# M220noadder.net
KiCad netlist of a schematic drawn in EAGLE
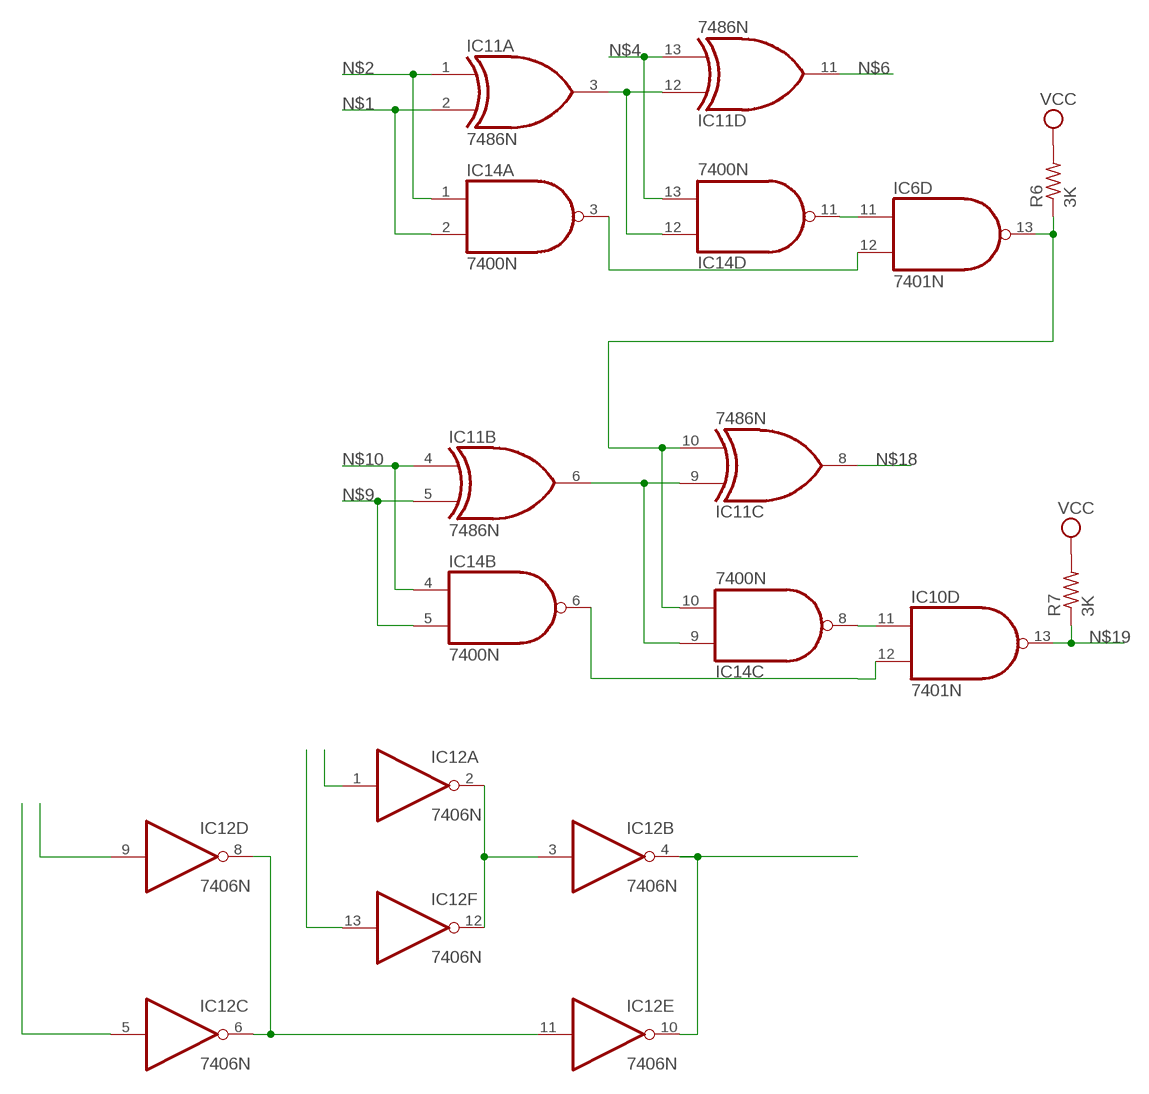
[diagram p0: schematic, sheet 1, part 1 of 2]
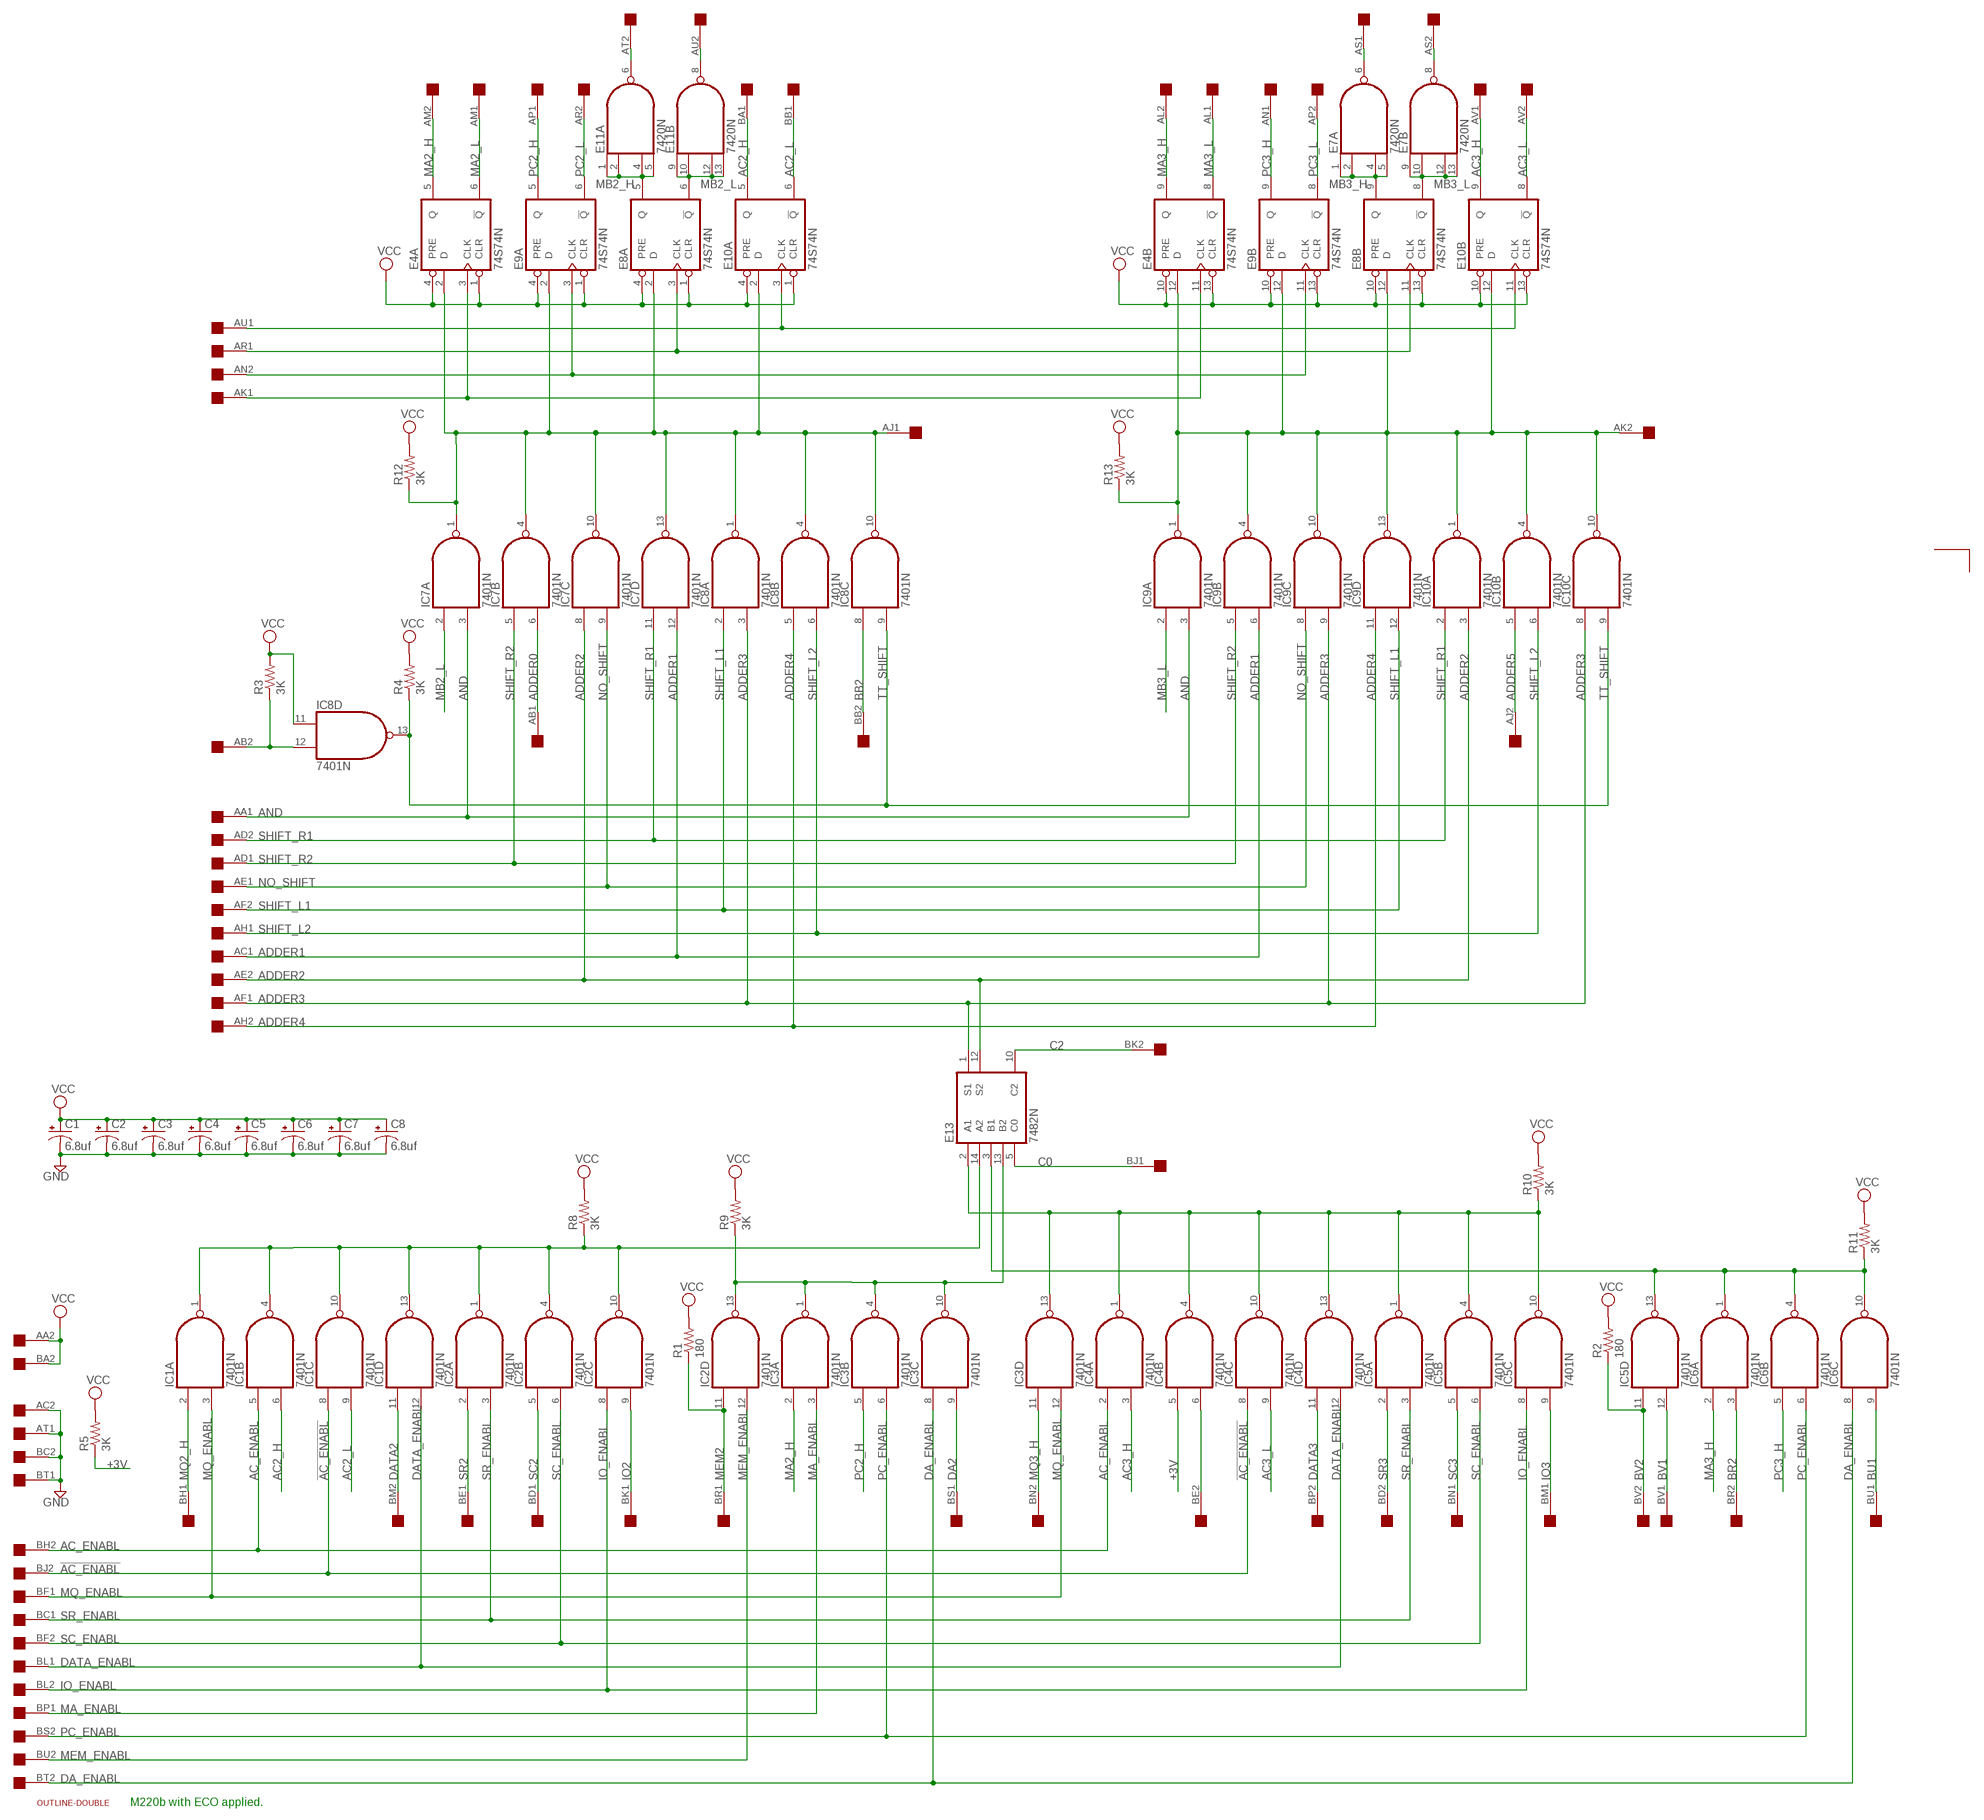
[diagram p1: schematic, sheet 1, part 2 of 2]

(export (version "E")
  (design (tool "Eeschema 10.0.6"))
  (components
    (comp (ref "C1")
      (value "6.8uf")
      (footprint "eagle-import:E15-5")
      (libsource (lib "eagle-import") (part "CPOL-USE15-5AXIAL"))
    )
    (comp (ref "C2")
      (value "6.8uf")
      (footprint "eagle-import:E15-5")
      (libsource (lib "eagle-import") (part "CPOL-USE15-5AXIAL"))
    )
    (comp (ref "C3")
      (value "6.8uf")
      (footprint "eagle-import:E15-5")
      (libsource (lib "eagle-import") (part "CPOL-USE15-5AXIAL"))
    )
    (comp (ref "C4")
      (value "6.8uf")
      (footprint "eagle-import:E15-5")
      (libsource (lib "eagle-import") (part "CPOL-USE15-5AXIAL"))
    )
    (comp (ref "C5")
      (value "6.8uf")
      (footprint "eagle-import:E15-5")
      (libsource (lib "eagle-import") (part "CPOL-USE15-5AXIAL"))
    )
    (comp (ref "C6")
      (value "6.8uf")
      (footprint "eagle-import:E15-5")
      (libsource (lib "eagle-import") (part "CPOL-USE15-5AXIAL"))
    )
    (comp (ref "C7")
      (value "6.8uf")
      (footprint "eagle-import:E15-5")
      (libsource (lib "eagle-import") (part "CPOL-USE15-5AXIAL"))
    )
    (comp (ref "C8")
      (value "6.8uf")
      (footprint "eagle-import:E15-5")
      (libsource (lib "eagle-import") (part "CPOL-USE15-5AXIAL"))
    )
    (comp (ref "E4")
      (value "74S74N")
      (footprint "eagle-import:DIL14")
      (libsource (lib "eagle-import") (part "7474NS"))
    )
    (comp (ref "E7")
      (value "7420N")
      (footprint "eagle-import:DIL14")
      (libsource (lib "eagle-import") (part "7420NS"))
    )
    (comp (ref "E8")
      (value "74S74N")
      (footprint "eagle-import:DIL14")
      (libsource (lib "eagle-import") (part "7474NS"))
    )
    (comp (ref "E9")
      (value "74S74N")
      (footprint "eagle-import:DIL14")
      (libsource (lib "eagle-import") (part "7474NS"))
    )
    (comp (ref "E10")
      (value "74S74N")
      (footprint "eagle-import:DIL14")
      (libsource (lib "eagle-import") (part "7474NS"))
    )
    (comp (ref "E11")
      (value "7420N")
      (footprint "eagle-import:DIL14")
      (libsource (lib "eagle-import") (part "7420NS"))
    )
    (comp (ref "E13")
      (value "7482N")
      (footprint "eagle-import:DIL14")
      (libsource (lib "eagle-import") (part "7482N"))
    )
    (comp (ref "IC1")
      (value "7401N")
      (footprint "eagle-import:DIL14")
      (libsource (lib "eagle-import") (part "7401N"))
    )
    (comp (ref "IC2")
      (value "7401N")
      (footprint "eagle-import:DIL14")
      (libsource (lib "eagle-import") (part "7401N"))
    )
    (comp (ref "IC3")
      (value "7401N")
      (footprint "eagle-import:DIL14")
      (libsource (lib "eagle-import") (part "7401N"))
    )
    (comp (ref "IC4")
      (value "7401N")
      (footprint "eagle-import:DIL14")
      (libsource (lib "eagle-import") (part "7401N"))
    )
    (comp (ref "IC5")
      (value "7401N")
      (footprint "eagle-import:DIL14")
      (libsource (lib "eagle-import") (part "7401N"))
    )
    (comp (ref "IC6")
      (value "7401N")
      (footprint "eagle-import:DIL14")
      (libsource (lib "eagle-import") (part "7401N"))
    )
    (comp (ref "IC7")
      (value "7401N")
      (footprint "eagle-import:DIL14")
      (libsource (lib "eagle-import") (part "7401N"))
    )
    (comp (ref "IC8")
      (value "7401N")
      (footprint "eagle-import:DIL14")
      (libsource (lib "eagle-import") (part "7401N"))
    )
    (comp (ref "IC9")
      (value "7401N")
      (footprint "eagle-import:DIL14")
      (libsource (lib "eagle-import") (part "7401N"))
    )
    (comp (ref "IC10")
      (value "7401N")
      (footprint "eagle-import:DIL14")
      (libsource (lib "eagle-import") (part "7401N"))
    )
    (comp (ref "IC11")
      (value "7486N")
      (footprint "eagle-import:DIL14")
      (libsource (lib "eagle-import") (part "7486N"))
    )
    (comp (ref "IC12")
      (value "7406N")
      (footprint "eagle-import:DIL14")
      (libsource (lib "eagle-import") (part "7406N"))
    )
    (comp (ref "IC14")
      (value "7400N")
      (footprint "eagle-import:DIL14")
      (libsource (lib "eagle-import") (part "7400N"))
    )
    (comp (ref "R1")
      (value "180")
      (footprint "eagle-import:0207_10")
      (libsource (lib "eagle-import") (part "R-US_0207/10"))
    )
    (comp (ref "R2")
      (value "180")
      (footprint "eagle-import:0207_10")
      (libsource (lib "eagle-import") (part "R-US_0207/10"))
    )
    (comp (ref "R3")
      (value "3K")
      (footprint "eagle-import:0207_10")
      (libsource (lib "eagle-import") (part "R-US_0207/10"))
    )
    (comp (ref "R4")
      (value "3K")
      (footprint "eagle-import:0207_10")
      (libsource (lib "eagle-import") (part "R-US_0207/10"))
    )
    (comp (ref "R5")
      (value "3K")
      (footprint "eagle-import:0207_10")
      (libsource (lib "eagle-import") (part "R-US_0207/10"))
    )
    (comp (ref "R6")
      (value "3K")
      (footprint "eagle-import:0207_10")
      (libsource (lib "eagle-import") (part "R-US_0207/10"))
    )
    (comp (ref "R7")
      (value "3K")
      (footprint "eagle-import:0207_10")
      (libsource (lib "eagle-import") (part "R-US_0207/10"))
    )
    (comp (ref "R8")
      (value "3K")
      (footprint "eagle-import:0207_10")
      (libsource (lib "eagle-import") (part "R-US_0207/10"))
    )
    (comp (ref "R9")
      (value "3K")
      (footprint "eagle-import:0207_10")
      (libsource (lib "eagle-import") (part "R-US_0207/10"))
    )
    (comp (ref "R10")
      (value "3K")
      (footprint "eagle-import:0207_10")
      (libsource (lib "eagle-import") (part "R-US_0207/10"))
    )
    (comp (ref "R11")
      (value "3K")
      (footprint "eagle-import:0207_10")
      (libsource (lib "eagle-import") (part "R-US_0207/10"))
    )
    (comp (ref "R12")
      (value "3K")
      (footprint "eagle-import:0207_10")
      (libsource (lib "eagle-import") (part "R-US_0207/10"))
    )
    (comp (ref "R13")
      (value "3K")
      (footprint "eagle-import:0207_10")
      (libsource (lib "eagle-import") (part "R-US_0207/10"))
    )
    (comp (ref "U$1")
      (value "DOUBLE")
      (footprint "eagle-import:EDGE-CON4")
      (libsource (lib "eagle-import") (part "DOUBLE"))
    )
    (comp (ref "U$2")
      (value "OUTLINE-DOUBLE")
      (footprint "eagle-import:DOUBLE")
      (libsource (lib "eagle-import") (part "OUTLINE-DOUBLE"))
    )
  )
  (nets
    (net (code "1") (name "/+3V") (class "Default")
      (node (ref "IC4") (pin "5") (pinfunction "I0_5") (pintype "input"))
      (node (ref "R5") (pin "1") (pinfunction "1_1") (pintype "passive"))
    )
    (net (code "2") (name "/AC2_H") (class "Default")
      (node (ref "E10") (pin "5") (pinfunction "Q_5") (pintype "output"))
      (node (ref "IC1") (pin "6") (pinfunction "I1_6") (pintype "input"))
      (node (ref "U$1") (pin "BA1") (pinfunction "1_BA1") (pintype "passive"))
    )
    (net (code "3") (name "/AC2_L") (class "Default")
      (node (ref "E10") (pin "6") (pinfunction "~{Q}_6") (pintype "output"))
      (node (ref "IC1") (pin "9") (pinfunction "I1_9") (pintype "input"))
      (node (ref "U$1") (pin "BB1") (pinfunction "1_BB1") (pintype "passive"))
    )
    (net (code "4") (name "/AC3_H") (class "Default")
      (node (ref "E10") (pin "9") (pinfunction "Q_9") (pintype "output"))
      (node (ref "IC4") (pin "3") (pinfunction "I1_3") (pintype "input"))
      (node (ref "U$1") (pin "AV1") (pinfunction "1_AV1") (pintype "passive"))
    )
    (net (code "5") (name "/AC3_L") (class "Default")
      (node (ref "E10") (pin "8") (pinfunction "~{Q}_8") (pintype "output"))
      (node (ref "IC4") (pin "9") (pinfunction "I1_9") (pintype "input"))
      (node (ref "U$1") (pin "AV2") (pinfunction "1_AV2") (pintype "passive"))
    )
    (net (code "6") (name "/AC_ENABL") (class "Default")
      (node (ref "IC1") (pin "5") (pinfunction "I0_5") (pintype "input"))
      (node (ref "IC4") (pin "2") (pinfunction "I0_2") (pintype "input"))
      (node (ref "U$1") (pin "BH2") (pinfunction "1_BH2") (pintype "passive"))
    )
    (net (code "7") (name "/ADDER0") (class "Default")
      (node (ref "IC7") (pin "6") (pinfunction "I1_6") (pintype "input"))
      (node (ref "U$1") (pin "AB1") (pinfunction "1_AB1") (pintype "passive"))
    )
    (net (code "8") (name "/ADDER1") (class "Default")
      (node (ref "IC7") (pin "12") (pinfunction "I1_12") (pintype "input"))
      (node (ref "IC9") (pin "6") (pinfunction "I1_6") (pintype "input"))
      (node (ref "U$1") (pin "AC1") (pinfunction "1_AC1") (pintype "passive"))
    )
    (net (code "9") (name "/ADDER2") (class "Default")
      (node (ref "E13") (pin "12") (pinfunction "S2_12") (pintype "output"))
      (node (ref "IC10") (pin "3") (pinfunction "I1_3") (pintype "input"))
      (node (ref "IC7") (pin "8") (pinfunction "I0_8") (pintype "input"))
      (node (ref "U$1") (pin "AE2") (pinfunction "1_AE2") (pintype "passive"))
    )
    (net (code "10") (name "/ADDER3") (class "Default")
      (node (ref "E13") (pin "1") (pinfunction "S1_1") (pintype "output"))
      (node (ref "IC10") (pin "8") (pinfunction "I0_8") (pintype "input"))
      (node (ref "IC8") (pin "3") (pinfunction "I1_3") (pintype "input"))
      (node (ref "IC9") (pin "9") (pinfunction "I1_9") (pintype "input"))
      (node (ref "U$1") (pin "AF1") (pinfunction "1_AF1") (pintype "passive"))
    )
    (net (code "11") (name "/ADDER4") (class "Default")
      (node (ref "IC8") (pin "5") (pinfunction "I0_5") (pintype "input"))
      (node (ref "IC9") (pin "11") (pinfunction "I0_11") (pintype "input"))
      (node (ref "U$1") (pin "AH2") (pinfunction "1_AH2") (pintype "passive"))
    )
    (net (code "12") (name "/ADDER5") (class "Default")
      (node (ref "IC10") (pin "5") (pinfunction "I0_5") (pintype "input"))
      (node (ref "U$1") (pin "AJ2") (pinfunction "1_AJ2") (pintype "passive"))
    )
    (net (code "13") (name "/AND") (class "Default")
      (node (ref "IC7") (pin "3") (pinfunction "I1_3") (pintype "input"))
      (node (ref "IC9") (pin "3") (pinfunction "I1_3") (pintype "input"))
      (node (ref "U$1") (pin "AA1") (pinfunction "1_AA1") (pintype "passive"))
    )
    (net (code "14") (name "/BB2") (class "Default")
      (node (ref "IC8") (pin "8") (pinfunction "I0_8") (pintype "input"))
      (node (ref "U$1") (pin "BB2") (pinfunction "1_BB2") (pintype "passive"))
    )
    (net (code "15") (name "/BR2") (class "Default")
      (node (ref "IC6") (pin "3") (pinfunction "I1_3") (pintype "input"))
      (node (ref "U$1") (pin "BR2") (pinfunction "1_BR2") (pintype "passive"))
    )
    (net (code "16") (name "/BU1") (class "Default")
      (node (ref "IC6") (pin "9") (pinfunction "I1_9") (pintype "input"))
      (node (ref "U$1") (pin "BU1") (pinfunction "1_BU1") (pintype "passive"))
    )
    (net (code "17") (name "/BV1") (class "Default")
      (node (ref "IC5") (pin "12") (pinfunction "I1_12") (pintype "input"))
      (node (ref "U$1") (pin "BV1") (pinfunction "1_BV1") (pintype "passive"))
    )
    (net (code "18") (name "/BV2") (class "Default")
      (node (ref "IC5") (pin "11") (pinfunction "I0_11") (pintype "input"))
      (node (ref "R2") (pin "1") (pinfunction "1_1") (pintype "passive"))
      (node (ref "U$1") (pin "BV2") (pinfunction "1_BV2") (pintype "passive"))
    )
    (net (code "19") (name "/C0") (class "Default")
      (node (ref "E13") (pin "5") (pinfunction "C0_5") (pintype "input"))
      (node (ref "U$1") (pin "BJ1") (pinfunction "1_BJ1") (pintype "passive"))
    )
    (net (code "20") (name "/C2") (class "Default")
      (node (ref "E13") (pin "10") (pinfunction "C2_10") (pintype "output"))
      (node (ref "U$1") (pin "BK2") (pinfunction "1_BK2") (pintype "passive"))
    )
    (net (code "21") (name "/DA2") (class "Default")
      (node (ref "IC3") (pin "9") (pinfunction "I1_9") (pintype "input"))
      (node (ref "U$1") (pin "BS1") (pinfunction "1_BS1") (pintype "passive"))
    )
    (net (code "22") (name "/DATA2") (class "Default")
      (node (ref "IC1") (pin "11") (pinfunction "I0_11") (pintype "input"))
      (node (ref "U$1") (pin "BM2") (pinfunction "1_BM2") (pintype "passive"))
    )
    (net (code "23") (name "/DATA3") (class "Default")
      (node (ref "IC4") (pin "11") (pinfunction "I0_11") (pintype "input"))
      (node (ref "U$1") (pin "BP2") (pinfunction "1_BP2") (pintype "passive"))
    )
    (net (code "24") (name "/DATA_ENABL") (class "Default")
      (node (ref "IC1") (pin "12") (pinfunction "I1_12") (pintype "input"))
      (node (ref "IC4") (pin "12") (pinfunction "I1_12") (pintype "input"))
      (node (ref "U$1") (pin "BL1") (pinfunction "1_BL1") (pintype "passive"))
    )
    (net (code "25") (name "/DA_ENABL") (class "Default")
      (node (ref "IC3") (pin "8") (pinfunction "I0_8") (pintype "input"))
      (node (ref "IC6") (pin "8") (pinfunction "I0_8") (pintype "input"))
      (node (ref "U$1") (pin "BT2") (pinfunction "1_BT2") (pintype "passive"))
    )
    (net (code "26") (name "/IO2") (class "Default")
      (node (ref "IC2") (pin "9") (pinfunction "I1_9") (pintype "input"))
      (node (ref "U$1") (pin "BK1") (pinfunction "1_BK1") (pintype "passive"))
    )
    (net (code "27") (name "/IO3") (class "Default")
      (node (ref "IC5") (pin "9") (pinfunction "I1_9") (pintype "input"))
      (node (ref "U$1") (pin "BM1") (pinfunction "1_BM1") (pintype "passive"))
    )
    (net (code "28") (name "/IO_ENABL") (class "Default")
      (node (ref "IC2") (pin "8") (pinfunction "I0_8") (pintype "input"))
      (node (ref "IC5") (pin "8") (pinfunction "I0_8") (pintype "input"))
      (node (ref "U$1") (pin "BL2") (pinfunction "1_BL2") (pintype "passive"))
    )
    (net (code "29") (name "/MA2_H") (class "Default")
      (node (ref "E4") (pin "5") (pinfunction "Q_5") (pintype "output"))
      (node (ref "IC3") (pin "2") (pinfunction "I0_2") (pintype "input"))
      (node (ref "U$1") (pin "AM2") (pinfunction "1_AM2") (pintype "passive"))
    )
    (net (code "30") (name "/MA2_L") (class "Default")
      (node (ref "E4") (pin "6") (pinfunction "~{Q}_6") (pintype "output"))
      (node (ref "U$1") (pin "AM1") (pinfunction "1_AM1") (pintype "passive"))
    )
    (net (code "31") (name "/MA3_H") (class "Default")
      (node (ref "E4") (pin "9") (pinfunction "Q_9") (pintype "output"))
      (node (ref "IC6") (pin "2") (pinfunction "I0_2") (pintype "input"))
      (node (ref "U$1") (pin "AL2") (pinfunction "1_AL2") (pintype "passive"))
    )
    (net (code "32") (name "/MA3_L") (class "Default")
      (node (ref "E4") (pin "8") (pinfunction "~{Q}_8") (pintype "output"))
      (node (ref "U$1") (pin "AL1") (pinfunction "1_AL1") (pintype "passive"))
    )
    (net (code "33") (name "/MA_ENABL") (class "Default")
      (node (ref "IC3") (pin "3") (pinfunction "I1_3") (pintype "input"))
      (node (ref "U$1") (pin "BP1") (pinfunction "1_BP1") (pintype "passive"))
    )
    (net (code "34") (name "/MB2_H") (class "Default")
      (node (ref "E11") (pin "1") (pinfunction "I0_1") (pintype "input"))
      (node (ref "E11") (pin "2") (pinfunction "I1_2") (pintype "input"))
      (node (ref "E11") (pin "4") (pinfunction "I2_4") (pintype "input"))
      (node (ref "E11") (pin "5") (pinfunction "I3_5") (pintype "input"))
      (node (ref "E8") (pin "5") (pinfunction "Q_5") (pintype "output"))
    )
    (net (code "35") (name "/MB2_L") (class "Default")
      (node (ref "E11") (pin "10") (pinfunction "I1_10") (pintype "input"))
      (node (ref "E11") (pin "12") (pinfunction "I2_12") (pintype "input"))
      (node (ref "E11") (pin "13") (pinfunction "I3_13") (pintype "input"))
      (node (ref "E11") (pin "9") (pinfunction "I0_9") (pintype "input"))
      (node (ref "E8") (pin "6") (pinfunction "~{Q}_6") (pintype "output"))
      (node (ref "IC7") (pin "2") (pinfunction "I0_2") (pintype "input"))
    )
    (net (code "36") (name "/MB3_H") (class "Default")
      (node (ref "E7") (pin "1") (pinfunction "I0_1") (pintype "input"))
      (node (ref "E7") (pin "2") (pinfunction "I1_2") (pintype "input"))
      (node (ref "E7") (pin "4") (pinfunction "I2_4") (pintype "input"))
      (node (ref "E7") (pin "5") (pinfunction "I3_5") (pintype "input"))
      (node (ref "E8") (pin "9") (pinfunction "Q_9") (pintype "output"))
    )
    (net (code "37") (name "/MB3_L") (class "Default")
      (node (ref "E7") (pin "10") (pinfunction "I1_10") (pintype "input"))
      (node (ref "E7") (pin "12") (pinfunction "I2_12") (pintype "input"))
      (node (ref "E7") (pin "13") (pinfunction "I3_13") (pintype "input"))
      (node (ref "E7") (pin "9") (pinfunction "I0_9") (pintype "input"))
      (node (ref "E8") (pin "8") (pinfunction "~{Q}_8") (pintype "output"))
      (node (ref "IC9") (pin "2") (pinfunction "I0_2") (pintype "input"))
    )
    (net (code "38") (name "/MEM2") (class "Default")
      (node (ref "IC2") (pin "11") (pinfunction "I0_11") (pintype "input"))
      (node (ref "R1") (pin "1") (pinfunction "1_1") (pintype "passive"))
      (node (ref "U$1") (pin "BR1") (pinfunction "1_BR1") (pintype "passive"))
    )
    (net (code "39") (name "/MEM_ENABL") (class "Default")
      (node (ref "IC2") (pin "12") (pinfunction "I1_12") (pintype "input"))
      (node (ref "U$1") (pin "BU2") (pinfunction "1_BU2") (pintype "passive"))
    )
    (net (code "40") (name "/MQ2_H") (class "Default")
      (node (ref "IC1") (pin "2") (pinfunction "I0_2") (pintype "input"))
      (node (ref "U$1") (pin "BH1") (pinfunction "1_BH1") (pintype "passive"))
    )
    (net (code "41") (name "/MQ3_H") (class "Default")
      (node (ref "IC3") (pin "11") (pinfunction "I0_11") (pintype "input"))
      (node (ref "U$1") (pin "BN2") (pinfunction "1_BN2") (pintype "passive"))
    )
    (net (code "42") (name "/MQ_ENABL") (class "Default")
      (node (ref "IC1") (pin "3") (pinfunction "I1_3") (pintype "input"))
      (node (ref "IC3") (pin "12") (pinfunction "I1_12") (pintype "input"))
      (node (ref "U$1") (pin "BF1") (pinfunction "1_BF1") (pintype "passive"))
    )
    (net (code "43") (name "/N$1") (class "Default")
      (node (ref "IC11") (pin "2") (pinfunction "I1_2") (pintype "input"))
      (node (ref "IC14") (pin "2") (pinfunction "I1_2") (pintype "input"))
    )
    (net (code "44") (name "/N$2") (class "Default")
      (node (ref "IC11") (pin "1") (pinfunction "I0_1") (pintype "input"))
      (node (ref "IC14") (pin "1") (pinfunction "I0_1") (pintype "input"))
    )
    (net (code "45") (name "/N$4") (class "Default")
      (node (ref "IC11") (pin "13") (pinfunction "I1_13") (pintype "input"))
      (node (ref "IC14") (pin "13") (pinfunction "I1_13") (pintype "input"))
    )
    (net (code "46") (name "/N$6") (class "Default")
      (node (ref "IC11") (pin "11") (pinfunction "O_11") (pintype "output"))
    )
    (net (code "47") (name "/N$9") (class "Default")
      (node (ref "IC11") (pin "5") (pinfunction "I1_5") (pintype "input"))
      (node (ref "IC14") (pin "5") (pinfunction "I1_5") (pintype "input"))
    )
    (net (code "48") (name "/N$10") (class "Default")
      (node (ref "IC11") (pin "4") (pinfunction "I0_4") (pintype "input"))
      (node (ref "IC14") (pin "4") (pinfunction "I0_4") (pintype "input"))
    )
    (net (code "49") (name "/N$18") (class "Default")
      (node (ref "IC11") (pin "8") (pinfunction "O_8") (pintype "output"))
    )
    (net (code "50") (name "/N$19") (class "Default")
      (node (ref "IC10") (pin "13") (pinfunction "O_13") (pintype "open_collector"))
      (node (ref "R7") (pin "1") (pinfunction "1_1") (pintype "passive"))
    )
    (net (code "51") (name "/NO_SHIFT") (class "Default")
      (node (ref "IC7") (pin "9") (pinfunction "I1_9") (pintype "input"))
      (node (ref "IC9") (pin "8") (pinfunction "I0_8") (pintype "input"))
      (node (ref "U$1") (pin "AE1") (pinfunction "1_AE1") (pintype "passive"))
    )
    (net (code "52") (name "/PC2_H") (class "Default")
      (node (ref "E9") (pin "5") (pinfunction "Q_5") (pintype "output"))
      (node (ref "IC3") (pin "5") (pinfunction "I0_5") (pintype "input"))
      (node (ref "U$1") (pin "AP1") (pinfunction "1_AP1") (pintype "passive"))
    )
    (net (code "53") (name "/PC2_L") (class "Default")
      (node (ref "E9") (pin "6") (pinfunction "~{Q}_6") (pintype "output"))
      (node (ref "U$1") (pin "AR2") (pinfunction "1_AR2") (pintype "passive"))
    )
    (net (code "54") (name "/PC3_H") (class "Default")
      (node (ref "E9") (pin "9") (pinfunction "Q_9") (pintype "output"))
      (node (ref "IC6") (pin "5") (pinfunction "I0_5") (pintype "input"))
      (node (ref "U$1") (pin "AN1") (pinfunction "1_AN1") (pintype "passive"))
    )
    (net (code "55") (name "/PC3_L") (class "Default")
      (node (ref "E9") (pin "8") (pinfunction "~{Q}_8") (pintype "output"))
      (node (ref "U$1") (pin "AP2") (pinfunction "1_AP2") (pintype "passive"))
    )
    (net (code "56") (name "/PC_ENABL") (class "Default")
      (node (ref "IC3") (pin "6") (pinfunction "I1_6") (pintype "input"))
      (node (ref "IC6") (pin "6") (pinfunction "I1_6") (pintype "input"))
      (node (ref "U$1") (pin "BS2") (pinfunction "1_BS2") (pintype "passive"))
    )
    (net (code "57") (name "/SC2") (class "Default")
      (node (ref "IC2") (pin "5") (pinfunction "I0_5") (pintype "input"))
      (node (ref "U$1") (pin "BD1") (pinfunction "1_BD1") (pintype "passive"))
    )
    (net (code "58") (name "/SC3") (class "Default")
      (node (ref "IC5") (pin "5") (pinfunction "I0_5") (pintype "input"))
      (node (ref "U$1") (pin "BN1") (pinfunction "1_BN1") (pintype "passive"))
    )
    (net (code "59") (name "/SC_ENABL") (class "Default")
      (node (ref "IC2") (pin "6") (pinfunction "I1_6") (pintype "input"))
      (node (ref "IC5") (pin "6") (pinfunction "I1_6") (pintype "input"))
      (node (ref "U$1") (pin "BF2") (pinfunction "1_BF2") (pintype "passive"))
    )
    (net (code "60") (name "/SHIFT_L1") (class "Default")
      (node (ref "IC8") (pin "2") (pinfunction "I0_2") (pintype "input"))
      (node (ref "IC9") (pin "12") (pinfunction "I1_12") (pintype "input"))
      (node (ref "U$1") (pin "AF2") (pinfunction "1_AF2") (pintype "passive"))
    )
    (net (code "61") (name "/SHIFT_L2") (class "Default")
      (node (ref "IC10") (pin "6") (pinfunction "I1_6") (pintype "input"))
      (node (ref "IC8") (pin "6") (pinfunction "I1_6") (pintype "input"))
      (node (ref "U$1") (pin "AH1") (pinfunction "1_AH1") (pintype "passive"))
    )
    (net (code "62") (name "/SHIFT_R1") (class "Default")
      (node (ref "IC10") (pin "2") (pinfunction "I0_2") (pintype "input"))
      (node (ref "IC7") (pin "11") (pinfunction "I0_11") (pintype "input"))
      (node (ref "U$1") (pin "AD2") (pinfunction "1_AD2") (pintype "passive"))
    )
    (net (code "63") (name "/SHIFT_R2") (class "Default")
      (node (ref "IC7") (pin "5") (pinfunction "I0_5") (pintype "input"))
      (node (ref "IC9") (pin "5") (pinfunction "I0_5") (pintype "input"))
      (node (ref "U$1") (pin "AD1") (pinfunction "1_AD1") (pintype "passive"))
    )
    (net (code "64") (name "/SR2") (class "Default")
      (node (ref "IC2") (pin "2") (pinfunction "I0_2") (pintype "input"))
      (node (ref "U$1") (pin "BE1") (pinfunction "1_BE1") (pintype "passive"))
    )
    (net (code "65") (name "/SR3") (class "Default")
      (node (ref "IC5") (pin "2") (pinfunction "I0_2") (pintype "input"))
      (node (ref "U$1") (pin "BD2") (pinfunction "1_BD2") (pintype "passive"))
    )
    (net (code "66") (name "/SR_ENABL") (class "Default")
      (node (ref "IC2") (pin "3") (pinfunction "I1_3") (pintype "input"))
      (node (ref "IC5") (pin "3") (pinfunction "I1_3") (pintype "input"))
      (node (ref "U$1") (pin "BC1") (pinfunction "1_BC1") (pintype "passive"))
    )
    (net (code "67") (name "/TT_SHIFT") (class "Default")
      (node (ref "IC10") (pin "9") (pinfunction "I1_9") (pintype "input"))
      (node (ref "IC8") (pin "13") (pinfunction "O_13") (pintype "open_collector"))
      (node (ref "IC8") (pin "9") (pinfunction "I1_9") (pintype "input"))
      (node (ref "R4") (pin "1") (pinfunction "1_1") (pintype "passive"))
    )
    (net (code "68") (name "/~{AC_ENABL}") (class "Default")
      (node (ref "IC1") (pin "8") (pinfunction "I0_8") (pintype "input"))
      (node (ref "IC4") (pin "8") (pinfunction "I0_8") (pintype "input"))
      (node (ref "U$1") (pin "BJ2") (pinfunction "1_BJ2") (pintype "passive"))
    )
    (net (code "69") (name "GND") (class "Default")
      (node (ref "C1") (pin "-") (pinfunction "-_-") (pintype "passive"))
      (node (ref "C2") (pin "-") (pinfunction "-_-") (pintype "passive"))
      (node (ref "C3") (pin "-") (pinfunction "-_-") (pintype "passive"))
      (node (ref "C4") (pin "-") (pinfunction "-_-") (pintype "passive"))
      (node (ref "C5") (pin "-") (pinfunction "-_-") (pintype "passive"))
      (node (ref "C6") (pin "-") (pinfunction "-_-") (pintype "passive"))
      (node (ref "C7") (pin "-") (pinfunction "-_-") (pintype "passive"))
      (node (ref "C8") (pin "-") (pinfunction "-_-") (pintype "passive"))
      (node (ref "U$1") (pin "AC2") (pinfunction "1_AC2") (pintype "passive"))
      (node (ref "U$1") (pin "AT1") (pinfunction "1_AT1") (pintype "passive"))
      (node (ref "U$1") (pin "BC2") (pinfunction "1_BC2") (pintype "passive"))
      (node (ref "U$1") (pin "BT1") (pinfunction "1_BT1") (pintype "passive"))
    )
    (net (code "70") (name "Net-(E4A-CLK)") (class "Default")
      (node (ref "E4") (pin "11") (pinfunction "CLK_11") (pintype "input"))
      (node (ref "E4") (pin "3") (pinfunction "CLK_3") (pintype "input"))
      (node (ref "U$1") (pin "AK1") (pinfunction "1_AK1") (pintype "passive"))
    )
    (net (code "71") (name "Net-(E7A-O)") (class "Default")
      (node (ref "E7") (pin "6") (pinfunction "O_6") (pintype "output"))
      (node (ref "U$1") (pin "AS1") (pinfunction "1_AS1") (pintype "passive"))
    )
    (net (code "72") (name "Net-(E7B-O)") (class "Default")
      (node (ref "E7") (pin "8") (pinfunction "O_8") (pintype "output"))
      (node (ref "U$1") (pin "AS2") (pinfunction "1_AS2") (pintype "passive"))
    )
    (net (code "73") (name "Net-(E8A-CLK)") (class "Default")
      (node (ref "E8") (pin "11") (pinfunction "CLK_11") (pintype "input"))
      (node (ref "E8") (pin "3") (pinfunction "CLK_3") (pintype "input"))
      (node (ref "U$1") (pin "AR1") (pinfunction "1_AR1") (pintype "passive"))
    )
    (net (code "74") (name "Net-(E9A-CLK)") (class "Default")
      (node (ref "E9") (pin "11") (pinfunction "CLK_11") (pintype "input"))
      (node (ref "E9") (pin "3") (pinfunction "CLK_3") (pintype "input"))
      (node (ref "U$1") (pin "AN2") (pinfunction "1_AN2") (pintype "passive"))
    )
    (net (code "75") (name "Net-(E10A-CLK)") (class "Default")
      (node (ref "E10") (pin "11") (pinfunction "CLK_11") (pintype "input"))
      (node (ref "E10") (pin "3") (pinfunction "CLK_3") (pintype "input"))
      (node (ref "U$1") (pin "AU1") (pinfunction "1_AU1") (pintype "passive"))
    )
    (net (code "76") (name "Net-(E10A-D)") (class "Default")
      (node (ref "E10") (pin "2") (pinfunction "D_2") (pintype "input"))
      (node (ref "E4") (pin "2") (pinfunction "D_2") (pintype "input"))
      (node (ref "E8") (pin "2") (pinfunction "D_2") (pintype "input"))
      (node (ref "E9") (pin "2") (pinfunction "D_2") (pintype "input"))
      (node (ref "IC7") (pin "1") (pinfunction "O_1") (pintype "open_collector"))
      (node (ref "IC7") (pin "10") (pinfunction "O_10") (pintype "open_collector"))
      (node (ref "IC7") (pin "13") (pinfunction "O_13") (pintype "open_collector"))
      (node (ref "IC7") (pin "4") (pinfunction "O_4") (pintype "open_collector"))
      (node (ref "IC8") (pin "1") (pinfunction "O_1") (pintype "open_collector"))
      (node (ref "IC8") (pin "10") (pinfunction "O_10") (pintype "open_collector"))
      (node (ref "IC8") (pin "4") (pinfunction "O_4") (pintype "open_collector"))
      (node (ref "R12") (pin "1") (pinfunction "1_1") (pintype "passive"))
      (node (ref "U$1") (pin "AJ1") (pinfunction "1_AJ1") (pintype "passive"))
    )
    (net (code "77") (name "Net-(E10B-D)") (class "Default")
      (node (ref "E10") (pin "12") (pinfunction "D_12") (pintype "input"))
      (node (ref "E4") (pin "12") (pinfunction "D_12") (pintype "input"))
      (node (ref "E8") (pin "12") (pinfunction "D_12") (pintype "input"))
      (node (ref "E9") (pin "12") (pinfunction "D_12") (pintype "input"))
      (node (ref "IC10") (pin "1") (pinfunction "O_1") (pintype "open_collector"))
      (node (ref "IC10") (pin "10") (pinfunction "O_10") (pintype "open_collector"))
      (node (ref "IC10") (pin "4") (pinfunction "O_4") (pintype "open_collector"))
      (node (ref "IC9") (pin "1") (pinfunction "O_1") (pintype "open_collector"))
      (node (ref "IC9") (pin "10") (pinfunction "O_10") (pintype "open_collector"))
      (node (ref "IC9") (pin "13") (pinfunction "O_13") (pintype "open_collector"))
      (node (ref "IC9") (pin "4") (pinfunction "O_4") (pintype "open_collector"))
      (node (ref "R13") (pin "1") (pinfunction "1_1") (pintype "passive"))
      (node (ref "U$1") (pin "AK2") (pinfunction "1_AK2") (pintype "passive"))
    )
    (net (code "78") (name "Net-(E11A-O)") (class "Default")
      (node (ref "E11") (pin "6") (pinfunction "O_6") (pintype "output"))
      (node (ref "U$1") (pin "AT2") (pinfunction "1_AT2") (pintype "passive"))
    )
    (net (code "79") (name "Net-(E11B-O)") (class "Default")
      (node (ref "E11") (pin "8") (pinfunction "O_8") (pintype "output"))
      (node (ref "U$1") (pin "AU2") (pinfunction "1_AU2") (pintype "passive"))
    )
    (net (code "80") (name "Net-(E13A-A1)") (class "Default")
      (node (ref "E13") (pin "2") (pinfunction "A1_2") (pintype "input"))
      (node (ref "IC3") (pin "13") (pinfunction "O_13") (pintype "open_collector"))
      (node (ref "IC4") (pin "1") (pinfunction "O_1") (pintype "open_collector"))
      (node (ref "IC4") (pin "10") (pinfunction "O_10") (pintype "open_collector"))
      (node (ref "IC4") (pin "13") (pinfunction "O_13") (pintype "open_collector"))
      (node (ref "IC4") (pin "4") (pinfunction "O_4") (pintype "open_collector"))
      (node (ref "IC5") (pin "1") (pinfunction "O_1") (pintype "open_collector"))
      (node (ref "IC5") (pin "10") (pinfunction "O_10") (pintype "open_collector"))
      (node (ref "IC5") (pin "4") (pinfunction "O_4") (pintype "open_collector"))
      (node (ref "R10") (pin "1") (pinfunction "1_1") (pintype "passive"))
    )
    (net (code "81") (name "Net-(E13A-A2)") (class "Default")
      (node (ref "E13") (pin "14") (pinfunction "A2_14") (pintype "input"))
      (node (ref "IC1") (pin "1") (pinfunction "O_1") (pintype "open_collector"))
      (node (ref "IC1") (pin "10") (pinfunction "O_10") (pintype "open_collector"))
      (node (ref "IC1") (pin "13") (pinfunction "O_13") (pintype "open_collector"))
      (node (ref "IC1") (pin "4") (pinfunction "O_4") (pintype "open_collector"))
      (node (ref "IC2") (pin "1") (pinfunction "O_1") (pintype "open_collector"))
      (node (ref "IC2") (pin "10") (pinfunction "O_10") (pintype "open_collector"))
      (node (ref "IC2") (pin "4") (pinfunction "O_4") (pintype "open_collector"))
      (node (ref "R8") (pin "1") (pinfunction "1_1") (pintype "passive"))
    )
    (net (code "82") (name "Net-(E13A-B1)") (class "Default")
      (node (ref "E13") (pin "3") (pinfunction "B1_3") (pintype "input"))
      (node (ref "IC5") (pin "13") (pinfunction "O_13") (pintype "open_collector"))
      (node (ref "IC6") (pin "1") (pinfunction "O_1") (pintype "open_collector"))
      (node (ref "IC6") (pin "10") (pinfunction "O_10") (pintype "open_collector"))
      (node (ref "IC6") (pin "4") (pinfunction "O_4") (pintype "open_collector"))
      (node (ref "R11") (pin "1") (pinfunction "1_1") (pintype "passive"))
    )
    (net (code "83") (name "Net-(E13A-B2)") (class "Default")
      (node (ref "E13") (pin "13") (pinfunction "B2_13") (pintype "input"))
      (node (ref "IC2") (pin "13") (pinfunction "O_13") (pintype "open_collector"))
      (node (ref "IC3") (pin "1") (pinfunction "O_1") (pintype "open_collector"))
      (node (ref "IC3") (pin "10") (pinfunction "O_10") (pintype "open_collector"))
      (node (ref "IC3") (pin "4") (pinfunction "O_4") (pintype "open_collector"))
      (node (ref "R9") (pin "1") (pinfunction "1_1") (pintype "passive"))
    )
    (net (code "84") (name "Net-(IC4B-I1)") (class "Default")
      (node (ref "IC4") (pin "6") (pinfunction "I1_6") (pintype "input"))
      (node (ref "U$1") (pin "BE2") (pinfunction "1_BE2") (pintype "passive"))
    )
    (net (code "85") (name "Net-(IC8D-I1)") (class "Default")
      (node (ref "IC8") (pin "12") (pinfunction "I1_12") (pintype "input"))
      (node (ref "R3") (pin "1") (pinfunction "1_1") (pintype "passive"))
      (node (ref "U$1") (pin "AB2") (pinfunction "1_AB2") (pintype "passive"))
    )
    (net (code "86") (name "Net-(IC10D-I0)") (class "Default")
      (node (ref "IC10") (pin "11") (pinfunction "I0_11") (pintype "input"))
      (node (ref "IC14") (pin "8") (pinfunction "O_8") (pintype "output"))
    )
    (net (code "87") (name "Net-(IC10D-I1)") (class "Default")
      (node (ref "IC10") (pin "12") (pinfunction "I1_12") (pintype "input"))
      (node (ref "IC14") (pin "6") (pinfunction "O_6") (pintype "output"))
    )
    (net (code "88") (name "Net-(IC11A-O)") (class "Default")
      (node (ref "IC11") (pin "12") (pinfunction "I0_12") (pintype "input"))
      (node (ref "IC11") (pin "3") (pinfunction "O_3") (pintype "output"))
      (node (ref "IC14") (pin "12") (pinfunction "I0_12") (pintype "input"))
    )
    (net (code "89") (name "Net-(IC11B-O)") (class "Default")
      (node (ref "IC11") (pin "6") (pinfunction "O_6") (pintype "output"))
      (node (ref "IC11") (pin "9") (pinfunction "I0_9") (pintype "input"))
      (node (ref "IC14") (pin "9") (pinfunction "I0_9") (pintype "input"))
    )
    (net (code "90") (name "Net-(IC11C-I1)") (class "Default")
      (node (ref "IC11") (pin "10") (pinfunction "I1_10") (pintype "input"))
      (node (ref "IC14") (pin "10") (pinfunction "I1_10") (pintype "input"))
      (node (ref "IC6") (pin "13") (pinfunction "O_13") (pintype "open_collector"))
      (node (ref "R6") (pin "1") (pinfunction "1_1") (pintype "passive"))
    )
    (net (code "91") (name "Net-(IC12A-O)") (class "Default")
      (node (ref "IC12") (pin "12") (pinfunction "O_12") (pintype "open_collector"))
      (node (ref "IC12") (pin "2") (pinfunction "O_2") (pintype "open_collector"))
      (node (ref "IC12") (pin "3") (pinfunction "I_3") (pintype "input"))
    )
    (net (code "92") (name "Net-(IC12B-O)") (class "Default")
      (node (ref "IC12") (pin "10") (pinfunction "O_10") (pintype "open_collector"))
      (node (ref "IC12") (pin "4") (pinfunction "O_4") (pintype "open_collector"))
    )
    (net (code "93") (name "Net-(IC12C-O)") (class "Default")
      (node (ref "IC12") (pin "11") (pinfunction "I_11") (pintype "input"))
      (node (ref "IC12") (pin "6") (pinfunction "O_6") (pintype "open_collector"))
      (node (ref "IC12") (pin "8") (pinfunction "O_8") (pintype "open_collector"))
    )
    (net (code "94") (name "Net-(IC14A-O)") (class "Default")
      (node (ref "IC14") (pin "3") (pinfunction "O_3") (pintype "output"))
      (node (ref "IC6") (pin "12") (pinfunction "I1_12") (pintype "input"))
    )
    (net (code "95") (name "Net-(IC14D-O)") (class "Default")
      (node (ref "IC14") (pin "11") (pinfunction "O_11") (pintype "output"))
      (node (ref "IC6") (pin "11") (pinfunction "I0_11") (pintype "input"))
    )
    (net (code "96") (name "VCC") (class "Default")
      (node (ref "C1") (pin "+") (pinfunction "+_+") (pintype "passive"))
      (node (ref "C2") (pin "+") (pinfunction "+_+") (pintype "passive"))
      (node (ref "C3") (pin "+") (pinfunction "+_+") (pintype "passive"))
      (node (ref "C4") (pin "+") (pinfunction "+_+") (pintype "passive"))
      (node (ref "C5") (pin "+") (pinfunction "+_+") (pintype "passive"))
      (node (ref "C6") (pin "+") (pinfunction "+_+") (pintype "passive"))
      (node (ref "C7") (pin "+") (pinfunction "+_+") (pintype "passive"))
      (node (ref "C8") (pin "+") (pinfunction "+_+") (pintype "passive"))
      (node (ref "E10") (pin "1") (pinfunction "CLR_1") (pintype "input"))
      (node (ref "E10") (pin "10") (pinfunction "PRE_10") (pintype "input"))
      (node (ref "E10") (pin "13") (pinfunction "CLR_13") (pintype "input"))
      (node (ref "E10") (pin "4") (pinfunction "PRE_4") (pintype "input"))
      (node (ref "E4") (pin "1") (pinfunction "CLR_1") (pintype "input"))
      (node (ref "E4") (pin "10") (pinfunction "PRE_10") (pintype "input"))
      (node (ref "E4") (pin "13") (pinfunction "CLR_13") (pintype "input"))
      (node (ref "E4") (pin "4") (pinfunction "PRE_4") (pintype "input"))
      (node (ref "E8") (pin "1") (pinfunction "CLR_1") (pintype "input"))
      (node (ref "E8") (pin "10") (pinfunction "PRE_10") (pintype "input"))
      (node (ref "E8") (pin "13") (pinfunction "CLR_13") (pintype "input"))
      (node (ref "E8") (pin "4") (pinfunction "PRE_4") (pintype "input"))
      (node (ref "E9") (pin "1") (pinfunction "CLR_1") (pintype "input"))
      (node (ref "E9") (pin "10") (pinfunction "PRE_10") (pintype "input"))
      (node (ref "E9") (pin "13") (pinfunction "CLR_13") (pintype "input"))
      (node (ref "E9") (pin "4") (pinfunction "PRE_4") (pintype "input"))
      (node (ref "IC8") (pin "11") (pinfunction "I0_11") (pintype "input"))
      (node (ref "R1") (pin "2") (pinfunction "2_2") (pintype "passive"))
      (node (ref "R10") (pin "2") (pinfunction "2_2") (pintype "passive"))
      (node (ref "R11") (pin "2") (pinfunction "2_2") (pintype "passive"))
      (node (ref "R12") (pin "2") (pinfunction "2_2") (pintype "passive"))
      (node (ref "R13") (pin "2") (pinfunction "2_2") (pintype "passive"))
      (node (ref "R2") (pin "2") (pinfunction "2_2") (pintype "passive"))
      (node (ref "R3") (pin "2") (pinfunction "2_2") (pintype "passive"))
      (node (ref "R4") (pin "2") (pinfunction "2_2") (pintype "passive"))
      (node (ref "R5") (pin "2") (pinfunction "2_2") (pintype "passive"))
      (node (ref "R6") (pin "2") (pinfunction "2_2") (pintype "passive"))
      (node (ref "R7") (pin "2") (pinfunction "2_2") (pintype "passive"))
      (node (ref "R8") (pin "2") (pinfunction "2_2") (pintype "passive"))
      (node (ref "R9") (pin "2") (pinfunction "2_2") (pintype "passive"))
      (node (ref "U$1") (pin "AA2") (pinfunction "1_AA2") (pintype "passive"))
      (node (ref "U$1") (pin "BA2") (pinfunction "1_BA2") (pintype "passive"))
    )
    (net (code "97") (name "unconnected-(IC12A-I-Pad1)") (class "Default")
      (node (ref "IC12") (pin "1") (pinfunction "I_1") (pintype "input"))
    )
    (net (code "98") (name "unconnected-(IC12C-I-Pad5)") (class "Default")
      (node (ref "IC12") (pin "5") (pinfunction "I_5") (pintype "input"))
    )
    (net (code "99") (name "unconnected-(IC12D-I-Pad9)") (class "Default")
      (node (ref "IC12") (pin "9") (pinfunction "I_9") (pintype "input"))
    )
    (net (code "100") (name "unconnected-(IC12F-I-Pad13)") (class "Default")
      (node (ref "IC12") (pin "13") (pinfunction "I_13") (pintype "input"))
    )
  )
)
